# Sheet1.net
KiCad netlist of a schematic drawn in Altium Designer
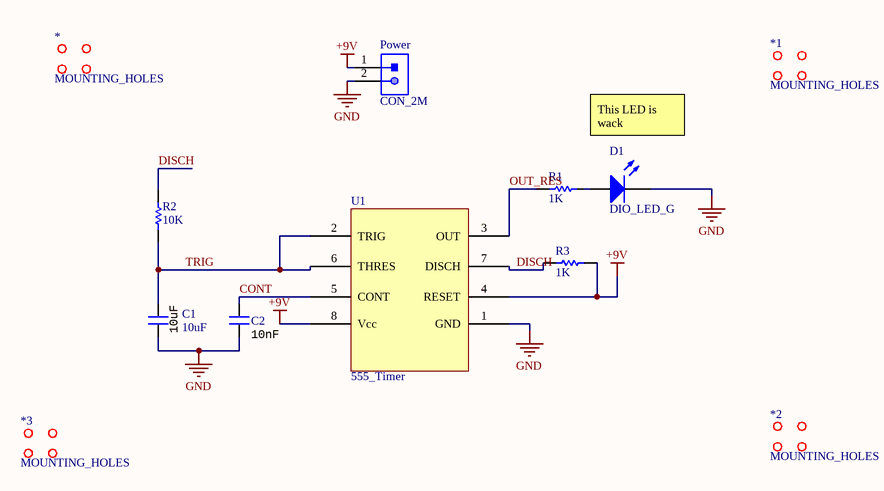
[diagram p0: Sheet1.SchDoc]

(export (version "E")
  (design (tool "Eeschema 10.0.6"))
  (components
    (comp (ref "*")
      (value "MOUNTING_HOLES")
      (footprint "MOUNTING_HOLE")
      (description "6cm x 6cm")
      (libsource (lib "UWRT_Schematic_Library_2020") (part "MOUNTING_HOLES"))
    )
    (comp (ref "*1")
      (value "MOUNTING_HOLES")
      (footprint "MOUNTING_HOLE")
      (description "6cm x 6cm")
      (libsource (lib "UWRT_Schematic_Library_2020") (part "MOUNTING_HOLES"))
    )
    (comp (ref "*2")
      (value "MOUNTING_HOLES")
      (footprint "MOUNTING_HOLE")
      (description "6cm x 6cm")
      (libsource (lib "UWRT_Schematic_Library_2020") (part "MOUNTING_HOLES"))
    )
    (comp (ref "*3")
      (value "MOUNTING_HOLES")
      (footprint "MOUNTING_HOLE")
      (description "6cm x 6cm")
      (libsource (lib "UWRT_Schematic_Library_2020") (part "MOUNTING_HOLES"))
    )
    (comp (ref "C1")
      (value "10uF")
      (footprint "CAPC0603(1608)55_N")
      (description "CAP CER 10UF 10V X5R 0603")
      (fields (field (name "MPN") "CC0603MRX5R6BB106") (field (name "MANUFACTURER") "Yageo"))
      (libsource (lib "UWRT_Schematic_Library_2020") (part "CAP_10uF_0603"))
    )
    (comp (ref "C2")
      (value "10nF")
      (footprint "CAPC0603(1608)55_N")
      (description "CAP CER 10000PF 16V X7R 0603")
      (fields (field (name "MPN") "CC0603KRX7R7BB103") (field (name "MANUFACTURER") "Yageo"))
      (libsource (lib "UWRT_Schematic_Library_2020") (part "CAP_10nF_0603"))
    )
    (comp (ref "D1")
      (value "DIO_LED_G")
      (footprint "LED_0805_LINE")
      (description "LED GREEN DIFFUSED 0805 SMD")
      (fields (field (name "MPN") "LG R971-KN-1") (field (name "MANUFACTURER") "OSRAM"))
      (libsource (lib "UWRT_Schematic_Library_2020") (part "DIO_LED_G"))
    )
    (comp (ref "Power")
      (value "CON_2M")
      (footprint "JST-B2B-PHSK")
      (libsource (lib "UWRT_Schematic_Library_2020") (part "CON_2M"))
    )
    (comp (ref "R1")
      (value "1K")
      (footprint "RESC0603(1608)_N")
      (description "RES SMD 1K OHM 5% 1/10W 0603")
      (fields (field (name "TOLERANCE") "5%") (field (name "MANUFACTURER") "Yageo"))
      (libsource (lib "UWRT_Schematic_Library_2020") (part "RES_1K_0603"))
    )
    (comp (ref "R2")
      (value "10K")
      (footprint "RESC0603(1608)_N")
      (description "RES SMD 10K OHM 5% 1/10W 0603")
      (fields (field (name "MANUFACTURER") "Yageo") (field (name "MPN") "RC0603JR-0710KL"))
      (libsource (lib "UWRT_Schematic_Library_2020") (part "RES_10K_0603"))
    )
    (comp (ref "R3")
      (value "1K")
      (footprint "RESC0603(1608)_N")
      (description "RES SMD 1K OHM 5% 1/10W 0603")
      (fields (field (name "TOLERANCE") "5%") (field (name "MANUFACTURER") "Yageo"))
      (libsource (lib "UWRT_Schematic_Library_2020") (part "RES_1K_0603"))
    )
    (comp (ref "U1") (value "555_Timer") (libsource (lib "UWRT_Schematic_Library_2020") (part "555_Timer")))
  )
  (nets
    (net (code "1") (name "+9V") (class "Default")
      (node (ref "Power") (pin "1") (pinfunction "1_1") (pintype "passive"))
      (node (ref "R3") (pin "2") (pinfunction "2_2") (pintype "passive"))
      (node (ref "U1") (pin "4") (pinfunction "RESET_4") (pintype "passive"))
      (node (ref "U1") (pin "8") (pinfunction "Vcc_8") (pintype "passive"))
    )
    (net (code "2") (name "/CONT") (class "Default")
      (node (ref "C2") (pin "2") (pinfunction "2_2") (pintype "passive"))
      (node (ref "U1") (pin "5") (pinfunction "CONT_5") (pintype "passive"))
    )
    (net (code "3") (name "/DISCH") (class "Default")
      (node (ref "R2") (pin "2") (pinfunction "2_2") (pintype "passive"))
      (node (ref "R3") (pin "1") (pinfunction "1_1") (pintype "passive"))
      (node (ref "U1") (pin "7") (pinfunction "DISCH_7") (pintype "passive"))
    )
    (net (code "4") (name "/OUT_RES") (class "Default")
      (node (ref "R1") (pin "1") (pinfunction "1_1") (pintype "passive"))
      (node (ref "U1") (pin "3") (pinfunction "OUT_3") (pintype "passive"))
    )
    (net (code "5") (name "/TRIG") (class "Default")
      (node (ref "C1") (pin "2") (pinfunction "2_2") (pintype "passive"))
      (node (ref "R2") (pin "1") (pinfunction "1_1") (pintype "passive"))
      (node (ref "U1") (pin "2") (pinfunction "TRIG_2") (pintype "passive"))
      (node (ref "U1") (pin "6") (pinfunction "THRES_6") (pintype "passive"))
    )
    (net (code "6") (name "GND") (class "Default")
      (node (ref "C1") (pin "1") (pinfunction "1_1") (pintype "passive"))
      (node (ref "C2") (pin "1") (pinfunction "1_1") (pintype "passive"))
      (node (ref "D1") (pin "2") (pinfunction "K_2") (pintype "passive"))
      (node (ref "Power") (pin "2") (pinfunction "2_2") (pintype "passive"))
      (node (ref "U1") (pin "1") (pinfunction "GND_1") (pintype "passive"))
    )
    (net (code "7") (name "Net-(D1-A)") (class "Default")
      (node (ref "D1") (pin "1") (pinfunction "A_1") (pintype "passive"))
      (node (ref "R1") (pin "2") (pinfunction "2_2") (pintype "passive"))
    )
  )
)
